# Medical_PCB.net
KiCad netlist of a schematic drawn in Altium Designer
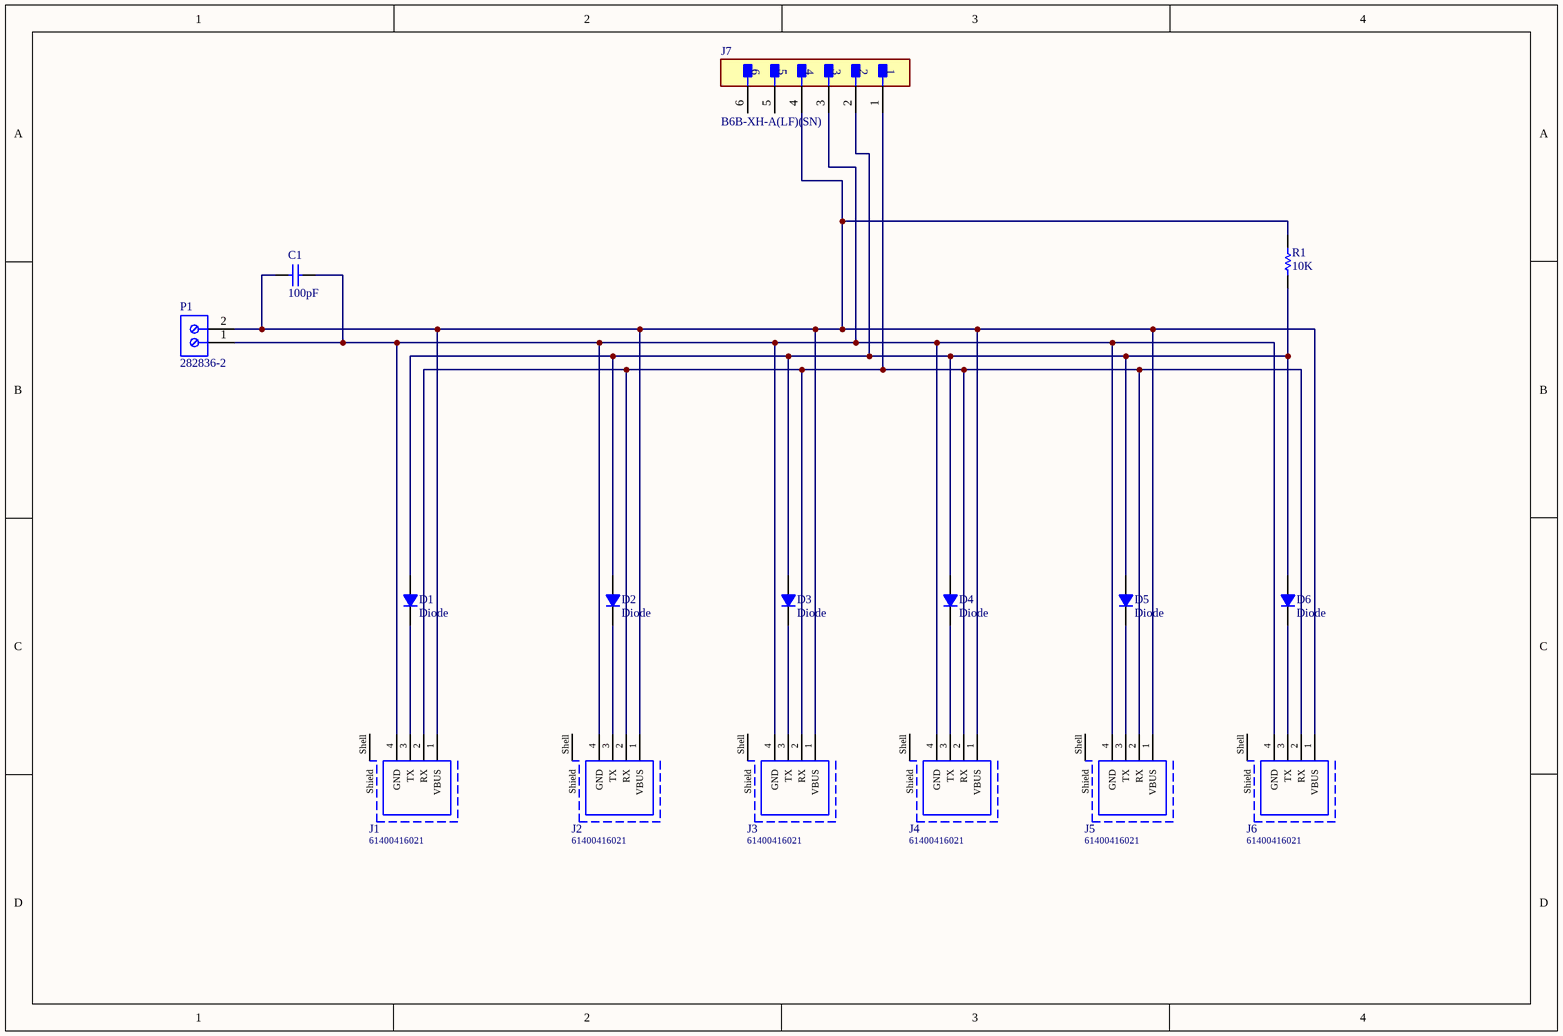
[diagram p0: Medical_PCB.SchDoc]

(export (version "E")
  (design (tool "Eeschema 10.0.6"))
  (components
    (comp (ref "C1")
      (value "100pF")
      (footprint "CAP 104")
      (description "Capacitor")
      (fields (field (name "Comment") "Cap") (field (name "PUBLISHER") "Altium Limited"))
      (libsource (lib "Nanjar's Library") (part "Cap"))
    )
    (comp (ref "D1")
      (value "Diode")
      (footprint "DIODE 4007")
      (description "Default Diode")
      (fields (field (name "PUBLISHER") "Altium Limited"))
      (libsource (lib "Nanjar's Library") (part "Diode"))
    )
    (comp (ref "D2")
      (value "Diode")
      (footprint "DIODE 4007")
      (description "Default Diode")
      (fields (field (name "PUBLISHER") "Altium Limited"))
      (libsource (lib "Nanjar's Library") (part "Diode"))
    )
    (comp (ref "D3")
      (value "Diode")
      (footprint "DIODE 4007")
      (description "Default Diode")
      (fields (field (name "PUBLISHER") "Altium Limited"))
      (libsource (lib "Nanjar's Library") (part "Diode"))
    )
    (comp (ref "D4")
      (value "Diode")
      (footprint "DIODE 4007")
      (description "Default Diode")
      (fields (field (name "PUBLISHER") "Altium Limited"))
      (libsource (lib "Nanjar's Library") (part "Diode"))
    )
    (comp (ref "D5")
      (value "Diode")
      (footprint "DIODE 4007")
      (description "Default Diode")
      (fields (field (name "PUBLISHER") "Altium Limited"))
      (libsource (lib "Nanjar's Library") (part "Diode"))
    )
    (comp (ref "D6")
      (value "Diode")
      (footprint "DIODE 4007")
      (description "Default Diode")
      (fields (field (name "PUBLISHER") "Altium Limited"))
      (libsource (lib "Nanjar's Library") (part "Diode"))
    )
    (comp (ref "J1")
      (value "61400416021")
      (footprint "61400416021")
      (description "USB 2.0 Type A Receptacle WR-COM, Horizontal, THT")
      (fields (field (name "MANUFACTURER") "Wurth Elektronik") (field (name "PUBLISHER") "WurthElektronik"))
      (libsource (lib "Altium Content Vault") (part "WE-USB-4-1SHLD"))
    )
    (comp (ref "J2")
      (value "61400416021")
      (footprint "61400416021")
      (description "USB 2.0 Type A Receptacle WR-COM, Horizontal, THT")
      (fields (field (name "MANUFACTURER") "Wurth Elektronik") (field (name "PUBLISHER") "WurthElektronik"))
      (libsource (lib "Altium Content Vault") (part "WE-USB-4-1SHLD"))
    )
    (comp (ref "J3")
      (value "61400416021")
      (footprint "61400416021")
      (description "USB 2.0 Type A Receptacle WR-COM, Horizontal, THT")
      (fields (field (name "MANUFACTURER") "Wurth Elektronik") (field (name "PUBLISHER") "WurthElektronik"))
      (libsource (lib "Altium Content Vault") (part "WE-USB-4-1SHLD"))
    )
    (comp (ref "J4")
      (value "61400416021")
      (footprint "61400416021")
      (description "USB 2.0 Type A Receptacle WR-COM, Horizontal, THT")
      (fields (field (name "MANUFACTURER") "Wurth Elektronik") (field (name "PUBLISHER") "WurthElektronik"))
      (libsource (lib "Altium Content Vault") (part "WE-USB-4-1SHLD"))
    )
    (comp (ref "J5")
      (value "61400416021")
      (footprint "61400416021")
      (description "USB 2.0 Type A Receptacle WR-COM, Horizontal, THT")
      (fields (field (name "MANUFACTURER") "Wurth Elektronik") (field (name "PUBLISHER") "WurthElektronik"))
      (libsource (lib "Altium Content Vault") (part "WE-USB-4-1SHLD"))
    )
    (comp (ref "J6")
      (value "61400416021")
      (footprint "61400416021")
      (description "USB 2.0 Type A Receptacle WR-COM, Horizontal, THT")
      (fields (field (name "MANUFACTURER") "Wurth Elektronik") (field (name "PUBLISHER") "WurthElektronik"))
      (libsource (lib "Altium Content Vault") (part "WE-USB-4-1SHLD"))
    )
    (comp (ref "J7")
      (value "B6B-XH-A(LF)(SN)")
      (footprint "FP-B6B-XH-A_LF_SN-MFG")
      (description "CONN HEADER VERT 6POS 2.5MM")
      (libsource (lib "Altium Content Vault") (part "f2cb566baf1c37ab5a3b8e90bbeafd6"))
    )
    (comp (ref "P1")
      (value "282836-2")
      (footprint "TECO-282836-2_V")
      (description "Female Header, Pitch 5 mm, 1 x 2 Position, Height 10 mm, Tail Length 3.5 mm, Rohs, Bulk")
      (fields (field (name "VOLTAGE") "300V") (field (name "MANUFACTURER") "TE Connectivity"))
      (libsource (lib "Altium Content Vault") (part "CN-1P-F-TB2"))
    )
    (comp (ref "R1")
      (value "10K")
      (footprint "Res 1/2WatT")
      (description "Resistor")
      (fields (field (name "PUBLISHER") "Altium Limited"))
      (libsource (lib "Nanjar's Library") (part "Resistor"))
    )
  )
  (nets
    (net (code "1") (name "Net-(D1-A)") (class "Default")
      (node (ref "D1") (pin "1") (pinfunction "A_1") (pintype "passive"))
      (node (ref "D2") (pin "1") (pinfunction "A_1") (pintype "passive"))
      (node (ref "D3") (pin "1") (pinfunction "A_1") (pintype "passive"))
      (node (ref "D4") (pin "1") (pinfunction "A_1") (pintype "passive"))
      (node (ref "D5") (pin "1") (pinfunction "A_1") (pintype "passive"))
      (node (ref "D6") (pin "1") (pinfunction "A_1") (pintype "passive"))
      (node (ref "J7") (pin "2") (pinfunction "2_2") (pintype "passive"))
      (node (ref "R1") (pin "2") (pinfunction "2_2") (pintype "passive"))
    )
    (net (code "2") (name "Net-(D1-K)") (class "Default")
      (node (ref "D1") (pin "2") (pinfunction "K_2") (pintype "passive"))
      (node (ref "J1") (pin "3") (pinfunction "TX_3") (pintype "passive"))
    )
    (net (code "3") (name "Net-(D2-K)") (class "Default")
      (node (ref "D2") (pin "2") (pinfunction "K_2") (pintype "passive"))
      (node (ref "J2") (pin "3") (pinfunction "TX_3") (pintype "passive"))
    )
    (net (code "4") (name "Net-(D3-K)") (class "Default")
      (node (ref "D3") (pin "2") (pinfunction "K_2") (pintype "passive"))
      (node (ref "J3") (pin "3") (pinfunction "TX_3") (pintype "passive"))
    )
    (net (code "5") (name "Net-(D4-K)") (class "Default")
      (node (ref "D4") (pin "2") (pinfunction "K_2") (pintype "passive"))
      (node (ref "J4") (pin "3") (pinfunction "TX_3") (pintype "passive"))
    )
    (net (code "6") (name "Net-(D5-K)") (class "Default")
      (node (ref "D5") (pin "2") (pinfunction "K_2") (pintype "passive"))
      (node (ref "J5") (pin "3") (pinfunction "TX_3") (pintype "passive"))
    )
    (net (code "7") (name "Net-(D6-K)") (class "Default")
      (node (ref "D6") (pin "2") (pinfunction "K_2") (pintype "passive"))
      (node (ref "J6") (pin "3") (pinfunction "TX_3") (pintype "passive"))
    )
    (net (code "8") (name "Net-(J1-GND)") (class "Default")
      (node (ref "C1") (pin "2") (pinfunction "2_2") (pintype "passive"))
      (node (ref "J1") (pin "4") (pinfunction "GND_4") (pintype "passive"))
      (node (ref "J2") (pin "4") (pinfunction "GND_4") (pintype "passive"))
      (node (ref "J3") (pin "4") (pinfunction "GND_4") (pintype "passive"))
      (node (ref "J4") (pin "4") (pinfunction "GND_4") (pintype "passive"))
      (node (ref "J5") (pin "4") (pinfunction "GND_4") (pintype "passive"))
      (node (ref "J6") (pin "4") (pinfunction "GND_4") (pintype "passive"))
      (node (ref "J7") (pin "3") (pinfunction "3_3") (pintype "passive"))
      (node (ref "P1") (pin "1") (pinfunction "1_1") (pintype "passive"))
    )
    (net (code "9") (name "Net-(J1-RX)") (class "Default")
      (node (ref "J1") (pin "2") (pinfunction "RX_2") (pintype "passive"))
      (node (ref "J2") (pin "2") (pinfunction "RX_2") (pintype "passive"))
      (node (ref "J3") (pin "2") (pinfunction "RX_2") (pintype "passive"))
      (node (ref "J4") (pin "2") (pinfunction "RX_2") (pintype "passive"))
      (node (ref "J5") (pin "2") (pinfunction "RX_2") (pintype "passive"))
      (node (ref "J6") (pin "2") (pinfunction "RX_2") (pintype "passive"))
      (node (ref "J7") (pin "1") (pinfunction "1_1") (pintype "passive"))
    )
    (net (code "10") (name "Net-(J1-VBUS)") (class "Default")
      (node (ref "C1") (pin "1") (pinfunction "1_1") (pintype "passive"))
      (node (ref "J1") (pin "1") (pinfunction "VBUS_1") (pintype "passive"))
      (node (ref "J2") (pin "1") (pinfunction "VBUS_1") (pintype "passive"))
      (node (ref "J3") (pin "1") (pinfunction "VBUS_1") (pintype "passive"))
      (node (ref "J4") (pin "1") (pinfunction "VBUS_1") (pintype "passive"))
      (node (ref "J5") (pin "1") (pinfunction "VBUS_1") (pintype "passive"))
      (node (ref "J6") (pin "1") (pinfunction "VBUS_1") (pintype "passive"))
      (node (ref "J7") (pin "4") (pinfunction "4_4") (pintype "passive"))
      (node (ref "P1") (pin "2") (pinfunction "2_2") (pintype "passive"))
      (node (ref "R1") (pin "1") (pinfunction "1_1") (pintype "passive"))
    )
    (net (code "11") (name "unconnected-(J1-Shield-PadShell)") (class "Default")
      (node (ref "J1") (pin "Shell") (pinfunction "Shield_Shell") (pintype "passive"))
    )
    (net (code "12") (name "unconnected-(J2-Shield-PadShell)") (class "Default")
      (node (ref "J2") (pin "Shell") (pinfunction "Shield_Shell") (pintype "passive"))
    )
    (net (code "13") (name "unconnected-(J3-Shield-PadShell)") (class "Default")
      (node (ref "J3") (pin "Shell") (pinfunction "Shield_Shell") (pintype "passive"))
    )
    (net (code "14") (name "unconnected-(J4-Shield-PadShell)") (class "Default")
      (node (ref "J4") (pin "Shell") (pinfunction "Shield_Shell") (pintype "passive"))
    )
    (net (code "15") (name "unconnected-(J5-Shield-PadShell)") (class "Default")
      (node (ref "J5") (pin "Shell") (pinfunction "Shield_Shell") (pintype "passive"))
    )
    (net (code "16") (name "unconnected-(J6-Shield-PadShell)") (class "Default")
      (node (ref "J6") (pin "Shell") (pinfunction "Shield_Shell") (pintype "passive"))
    )
    (net (code "17") (name "unconnected-(J7-Pad5)") (class "Default")
      (node (ref "J7") (pin "5") (pinfunction "5_5") (pintype "passive"))
    )
    (net (code "18") (name "unconnected-(J7-Pad6)") (class "Default")
      (node (ref "J7") (pin "6") (pinfunction "6_6") (pintype "passive"))
    )
  )
)
